# wifi.net
KiCad netlist of a schematic drawn in Altium Designer
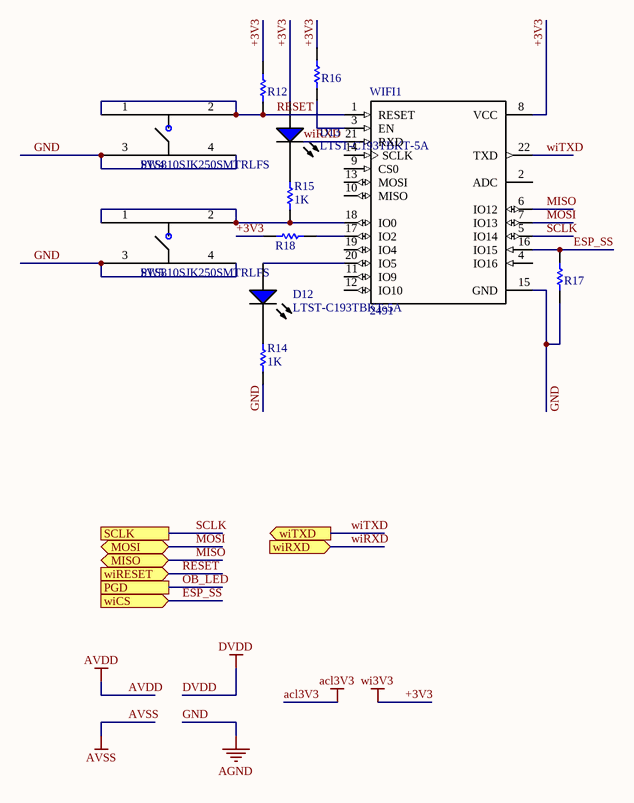
[diagram p0: wifi.SchDoc]

(export (version "E")
  (design (tool "Eeschema 10.0.6"))
  (components
    (comp (ref "D12")
      (value "LTST-C193TBKT-5A")
      (footprint "LTST-C193TBKT_V")
      (description "LED BLUE CLEAR CHIP SMD")
      (libsource (lib "EE_smallOB_BW_v1.0") (part "LTST-C193TBKT-5A"))
    )
    (comp (ref "D13")
      (value "LTST-C193TBKT-5A")
      (footprint "LTST-C193TBKT_V")
      (description "LED BLUE CLEAR CHIP SMD")
      (libsource (lib "EE_smallOB_BW_v1.0") (part "LTST-C193TBKT-5A"))
    )
    (comp (ref "R12")
      (value "10K")
      (footprint "RESC1609X55X30NL15T15")
      (description "Res Thick Film 0603 10K Ohm 1% 1/10W ±100ppm/°C Molded SMD Punched Carrier T/R")
      (fields (field (name "TOLERANCE") "1%"))
      (libsource (lib "EE_smallOB_BW_v1.0") (part "ERJ-3EKF1002V"))
    )
    (comp (ref "R14")
      (value "1K")
      (footprint "RESC1609X55X30NL15T15")
      (description "Res Thick Film 0603 1K Ohm 1% 1/10W ±100ppm/°C Molded SMD Punched Carrier T/R")
      (fields (field (name "TOLERANCE") "1%"))
      (libsource (lib "EE_smallOB_BW_v1.0") (part "ERJ3EKF1001V"))
    )
    (comp (ref "R15")
      (value "1K")
      (footprint "RESC1609X55X30NL15T15")
      (description "Res Thick Film 0603 1K Ohm 1% 1/10W ±100ppm/°C Molded SMD Punched Carrier T/R")
      (fields (field (name "TOLERANCE") "1%"))
      (libsource (lib "EE_smallOB_BW_v1.0") (part "ERJ3EKF1001V"))
    )
    (comp (ref "R16")
      (value "10K")
      (footprint "RESC1609X55X30NL15T15")
      (description "Res Thick Film 0603 10K Ohm 1% 1/10W ±100ppm/°C Molded SMD Punched Carrier T/R")
      (fields (field (name "TOLERANCE") "1%"))
      (libsource (lib "EE_smallOB_BW_v1.0") (part "ERJ-3EKF1002V"))
    )
    (comp (ref "R17")
      (value "10K")
      (footprint "RESC1609X55X30NL15T15")
      (description "Res Thick Film 0603 10K Ohm 1% 1/10W ±100ppm/°C Molded SMD Punched Carrier T/R")
      (fields (field (name "TOLERANCE") "1%"))
      (libsource (lib "EE_smallOB_BW_v1.0") (part "ERJ-3EKF1002V"))
    )
    (comp (ref "R18")
      (value "10K")
      (footprint "RESC1609X55X30NL15T15")
      (description "Res Thick Film 0603 10K Ohm 1% 1/10W ±100ppm/°C Molded SMD Punched Carrier T/R")
      (fields (field (name "TOLERANCE") "1%"))
      (libsource (lib "EE_smallOB_BW_v1.0") (part "ERJ-3EKF1002V"))
    )
    (comp (ref "SW4")
      (value "PTS810SJK250SMTRLFS")
      (footprint "PTS810")
      (description "SWITCH TACTILE SPST-NO 0.05A 16V")
      (libsource (lib "EE_smallOB_BW_v1.0") (part "PTS810SJK250SMTRLFS"))
    )
    (comp (ref "SW5")
      (value "PTS810SJK250SMTRLFS")
      (footprint "PTS810")
      (description "SWITCH TACTILE SPST-NO 0.05A 16V")
      (libsource (lib "EE_smallOB_BW_v1.0") (part "PTS810SJK250SMTRLFS"))
    )
    (comp (ref "WIFI1")
      (value "2491")
      (footprint "*XCVR_ESP8266-12E/ESP-12E")
      (description "ESP8266 SMT MODULE")
      (libsource (lib "EE_smallOB_BW_v1.0") (part "2491"))
    )
  )
  (nets
    (net (code "1") (name "/ESP_SS") (class "Default")
      (node (ref "R17") (pin "2") (pinfunction "2_2") (pintype "passive"))
      (node (ref "WIFI1") (pin "16") (pinfunction "IO15_16") (pintype "input"))
    )
    (net (code "2") (name "/MISO") (class "Default")
      (node (ref "WIFI1") (pin "6") (pinfunction "IO12_6") (pintype "bidirectional"))
    )
    (net (code "3") (name "/MOSI") (class "Default")
      (node (ref "WIFI1") (pin "7") (pinfunction "IO13_7") (pintype "bidirectional"))
    )
    (net (code "5") (name "/RESET") (class "Default")
      (node (ref "R12") (pin "1") (pinfunction "1_1") (pintype "passive"))
      (node (ref "SW4") (pin "1") (pinfunction "1_1") (pintype "passive"))
      (node (ref "SW4") (pin "2") (pinfunction "2_2") (pintype "passive"))
      (node (ref "WIFI1") (pin "1") (pinfunction "RESET_1") (pintype "input"))
    )
    (net (code "6") (name "/SCLK") (class "Default")
      (node (ref "WIFI1") (pin "5") (pinfunction "IO14_5") (pintype "bidirectional"))
    )
    (net (code "7") (name "/wiRXD") (class "Default")
      (node (ref "WIFI1") (pin "21") (pinfunction "RXD_21") (pintype "input"))
    )
    (net (code "8") (name "/wiTXD") (class "Default")
      (node (ref "WIFI1") (pin "22") (pinfunction "TXD_22") (pintype "output"))
    )
    (net (code "9") (name "AGND") (class "Default")
      (node (ref "R14") (pin "1") (pinfunction "1_1") (pintype "passive"))
      (node (ref "R17") (pin "1") (pinfunction "1_1") (pintype "passive"))
      (node (ref "SW4") (pin "3") (pinfunction "3_3") (pintype "passive"))
      (node (ref "SW4") (pin "4") (pinfunction "4_4") (pintype "passive"))
      (node (ref "SW5") (pin "3") (pinfunction "3_3") (pintype "passive"))
      (node (ref "SW5") (pin "4") (pinfunction "4_4") (pintype "passive"))
      (node (ref "WIFI1") (pin "15") (pinfunction "GND_15") (pintype "power_in"))
    )
    (net (code "13") (name "Net-(D12-A)") (class "Default")
      (node (ref "D12") (pin "1") (pinfunction "A_1") (pintype "passive"))
      (node (ref "WIFI1") (pin "20") (pinfunction "IO5_20") (pintype "bidirectional"))
    )
    (net (code "14") (name "Net-(D12-K)") (class "Default")
      (node (ref "D12") (pin "2") (pinfunction "K_2") (pintype "passive"))
      (node (ref "R14") (pin "2") (pinfunction "2_2") (pintype "passive"))
    )
    (net (code "15") (name "Net-(D13-K)") (class "Default")
      (node (ref "D13") (pin "2") (pinfunction "K_2") (pintype "passive"))
      (node (ref "R15") (pin "2") (pinfunction "2_2") (pintype "passive"))
    )
    (net (code "16") (name "Net-(WIFI1-EN)") (class "Default")
      (node (ref "R16") (pin "1") (pinfunction "1_1") (pintype "passive"))
      (node (ref "WIFI1") (pin "3") (pinfunction "EN_3") (pintype "input"))
    )
    (net (code "17") (name "Net-(WIFI1-IO0)") (class "Default")
      (node (ref "R15") (pin "1") (pinfunction "1_1") (pintype "passive"))
      (node (ref "SW5") (pin "1") (pinfunction "1_1") (pintype "passive"))
      (node (ref "SW5") (pin "2") (pinfunction "2_2") (pintype "passive"))
      (node (ref "WIFI1") (pin "18") (pinfunction "IO0_18") (pintype "bidirectional"))
    )
    (net (code "18") (name "Net-(WIFI1-IO2)") (class "Default")
      (node (ref "R18") (pin "1") (pinfunction "1_1") (pintype "passive"))
      (node (ref "WIFI1") (pin "17") (pinfunction "IO2_17") (pintype "bidirectional"))
    )
    (net (code "20") (name "unconnected-(WIFI1-ADC-Pad2)") (class "Default")
      (node (ref "WIFI1") (pin "2") (pinfunction "ADC_2") (pintype "passive"))
    )
    (net (code "21") (name "unconnected-(WIFI1-CS0-Pad9)") (class "Default")
      (node (ref "WIFI1") (pin "9") (pinfunction "CS0_9") (pintype "input"))
    )
    (net (code "22") (name "unconnected-(WIFI1-IO4-Pad19)") (class "Default")
      (node (ref "WIFI1") (pin "19") (pinfunction "IO4_19") (pintype "bidirectional"))
    )
    (net (code "23") (name "unconnected-(WIFI1-IO9-Pad11)") (class "Default")
      (node (ref "WIFI1") (pin "11") (pinfunction "IO9_11") (pintype "bidirectional"))
    )
    (net (code "24") (name "unconnected-(WIFI1-IO10-Pad12)") (class "Default")
      (node (ref "WIFI1") (pin "12") (pinfunction "IO10_12") (pintype "bidirectional"))
    )
    (net (code "25") (name "unconnected-(WIFI1-IO16-Pad4)") (class "Default")
      (node (ref "WIFI1") (pin "4") (pinfunction "IO16_4") (pintype "input"))
    )
    (net (code "26") (name "unconnected-(WIFI1-MISO-Pad10)") (class "Default")
      (node (ref "WIFI1") (pin "10") (pinfunction "MISO_10") (pintype "bidirectional"))
    )
    (net (code "27") (name "unconnected-(WIFI1-MOSI-Pad13)") (class "Default")
      (node (ref "WIFI1") (pin "13") (pinfunction "MOSI_13") (pintype "bidirectional"))
    )
    (net (code "28") (name "unconnected-(WIFI1-SCLK-Pad14)") (class "Default")
      (node (ref "WIFI1") (pin "14") (pinfunction "SCLK_14") (pintype "input"))
    )
    (net (code "29") (name "wi3V3") (class "Default")
      (node (ref "D13") (pin "1") (pinfunction "A_1") (pintype "passive"))
      (node (ref "R12") (pin "2") (pinfunction "2_2") (pintype "passive"))
      (node (ref "R16") (pin "2") (pinfunction "2_2") (pintype "passive"))
      (node (ref "R18") (pin "2") (pinfunction "2_2") (pintype "passive"))
      (node (ref "WIFI1") (pin "8") (pinfunction "VCC_8") (pintype "power_in"))
    )
  )
)
